# MAIN_TOP_P.net
KiCad netlist of a schematic drawn in EAGLE
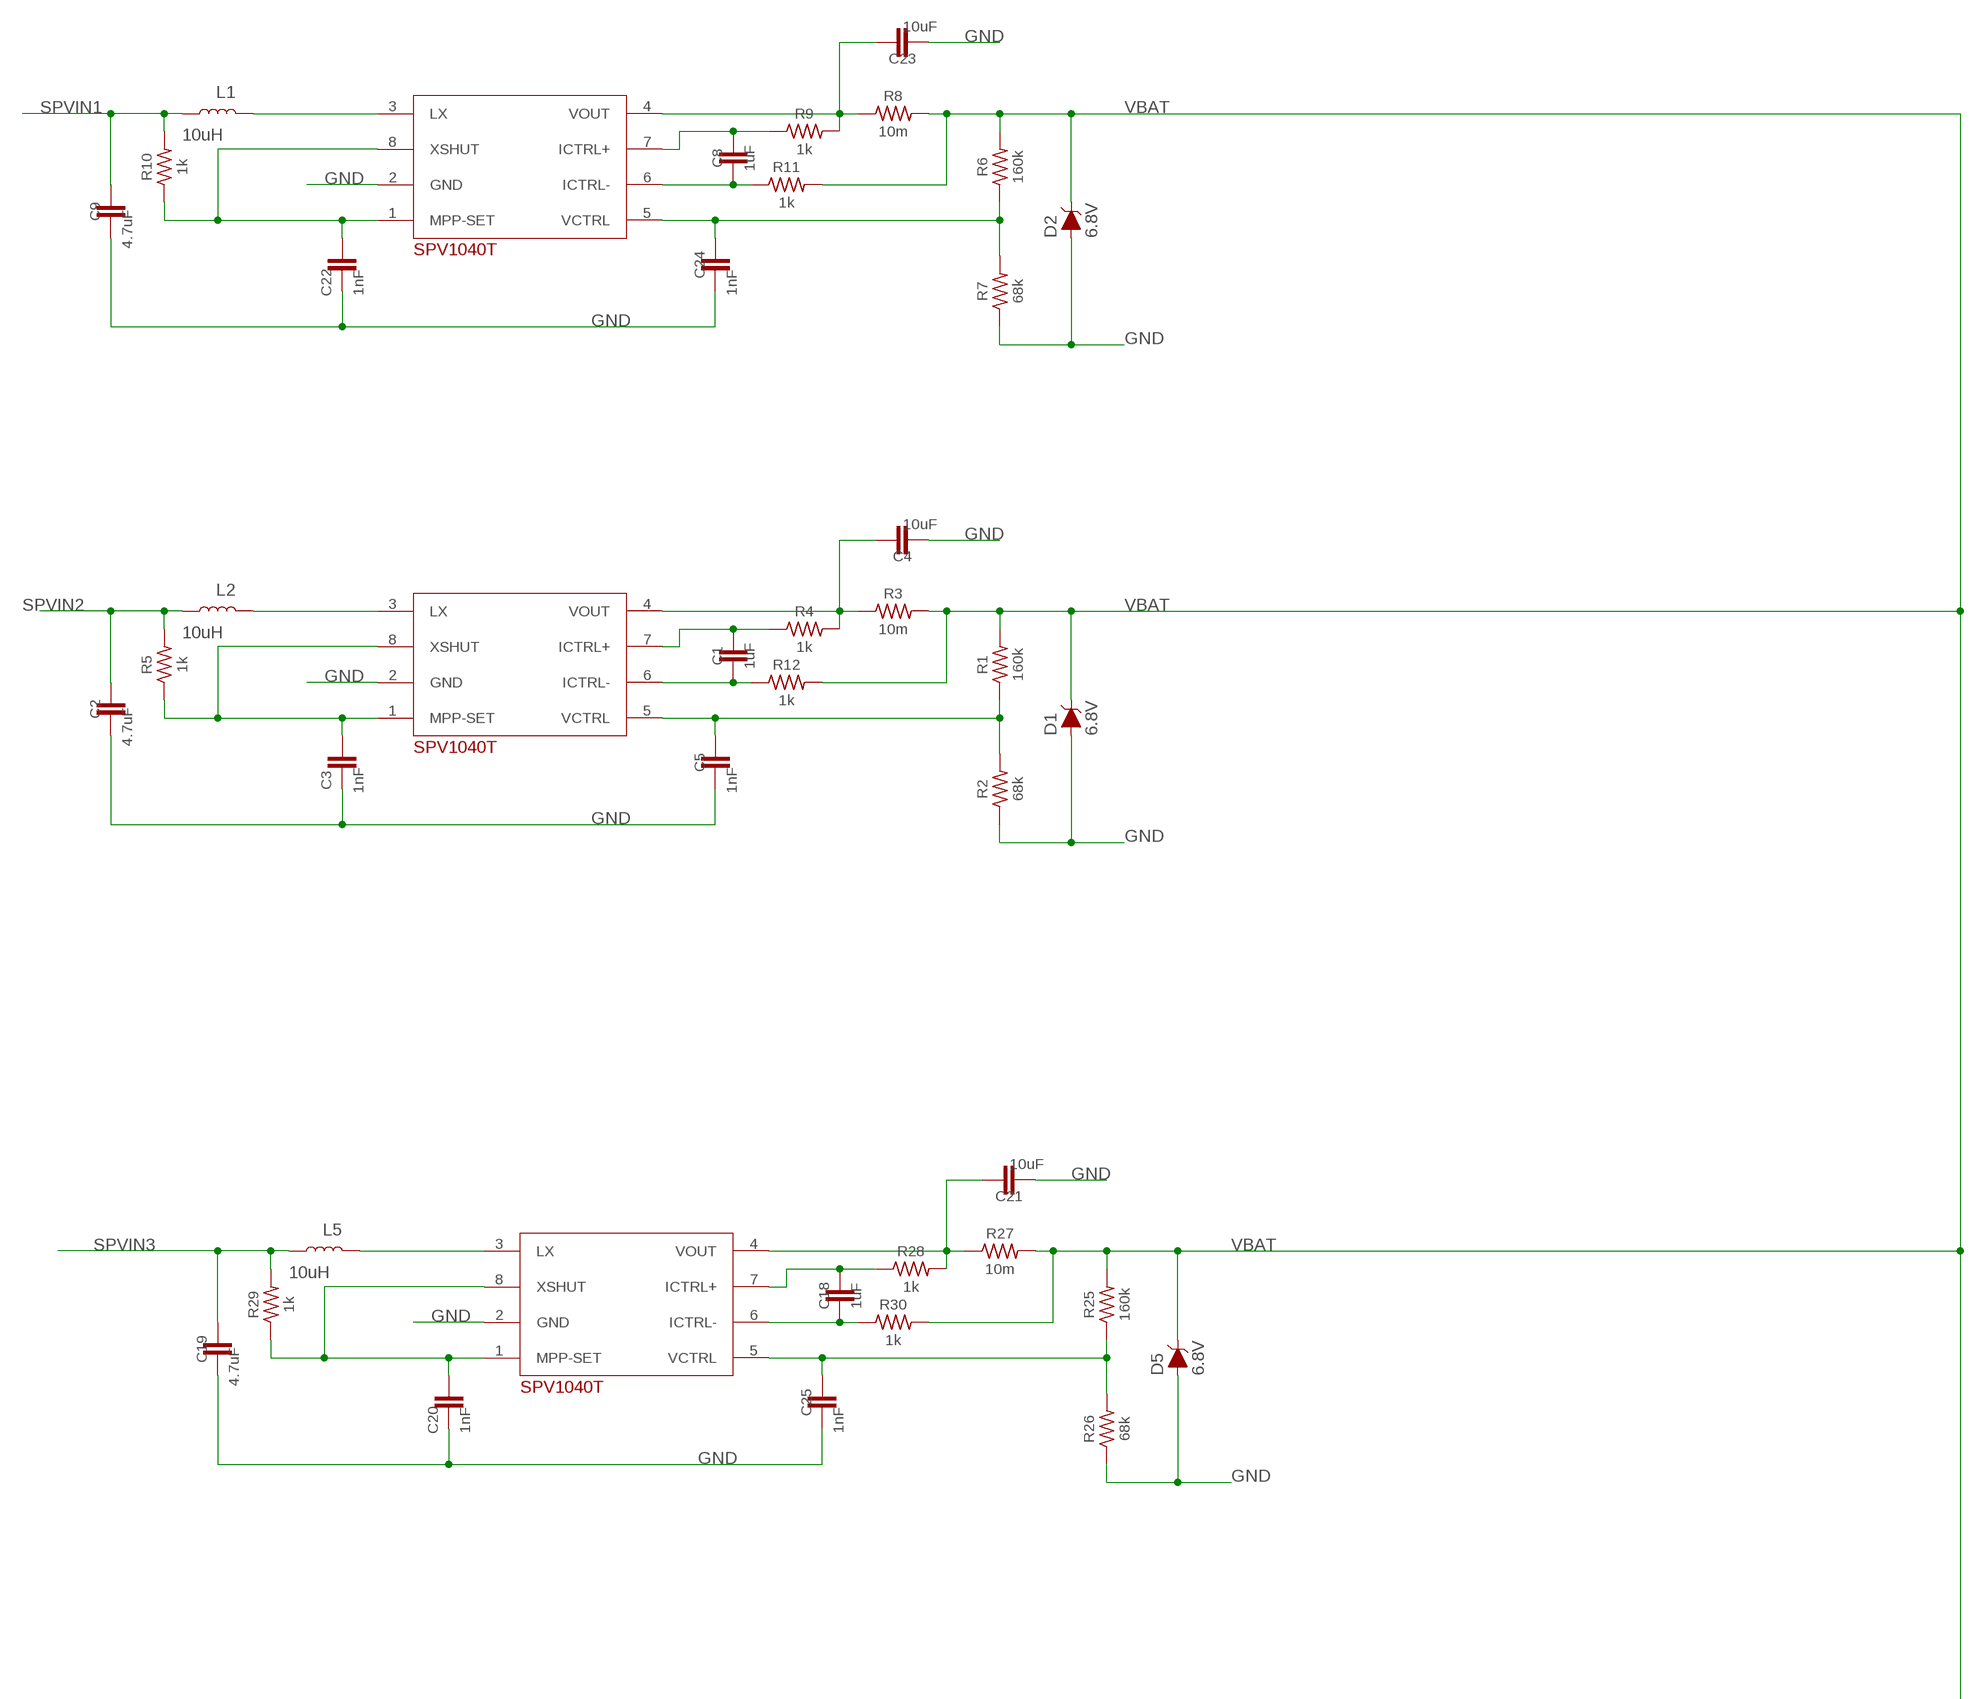
[diagram p0: schematic, sheet 1, part 1 of 3]
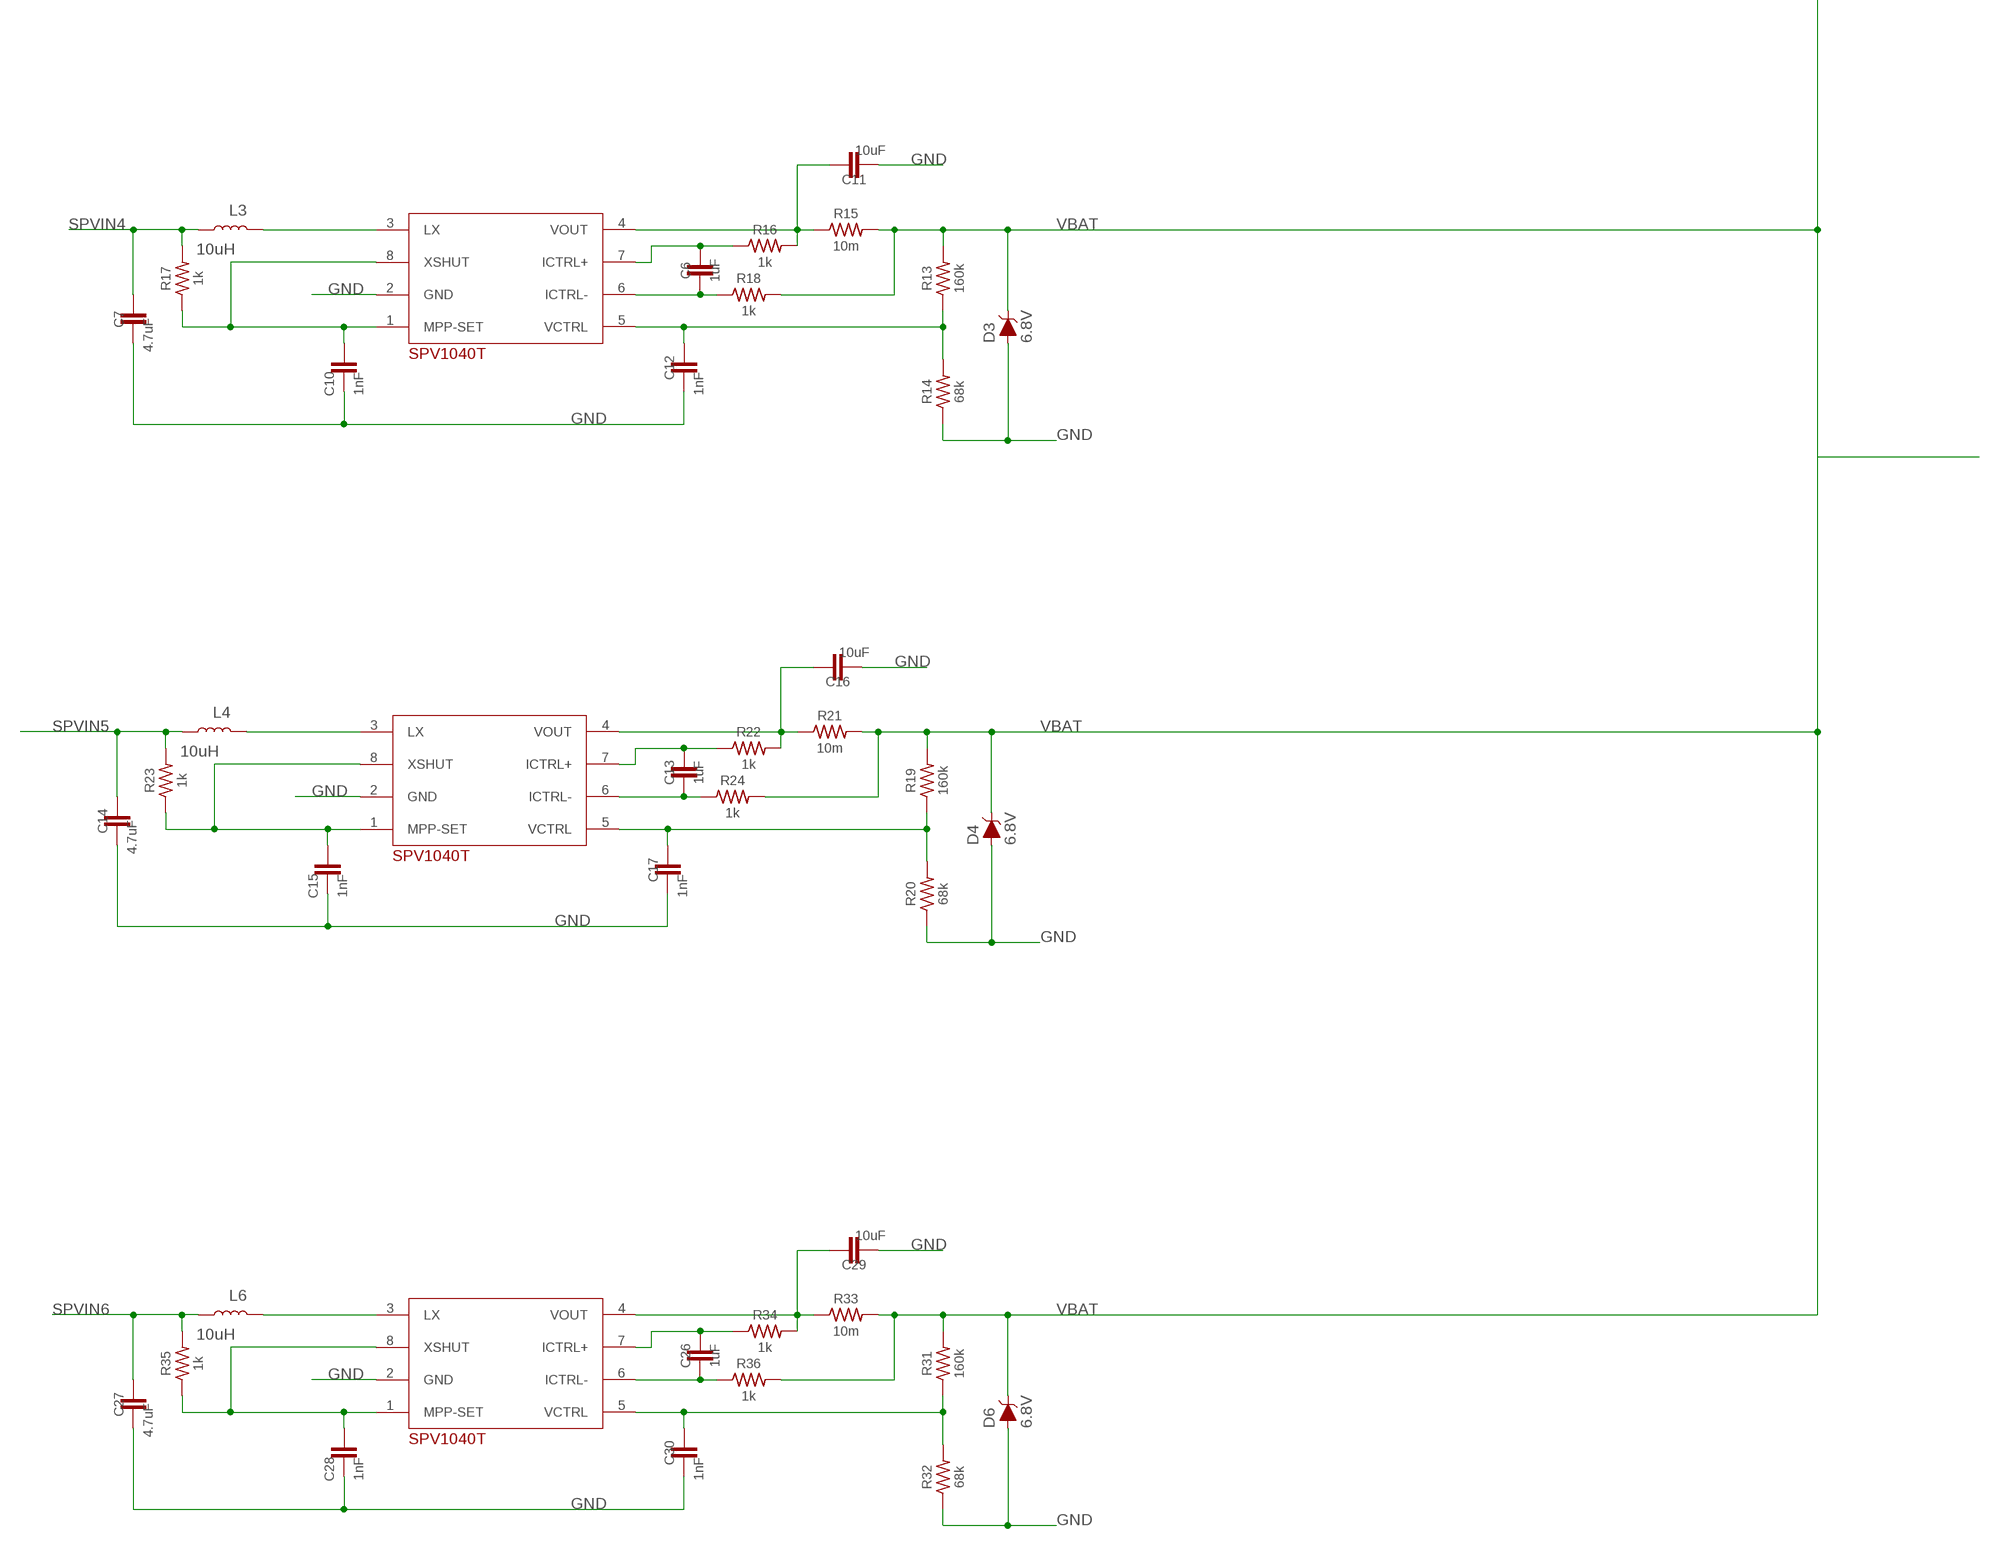
[diagram p1: schematic, sheet 1, part 2 of 3]
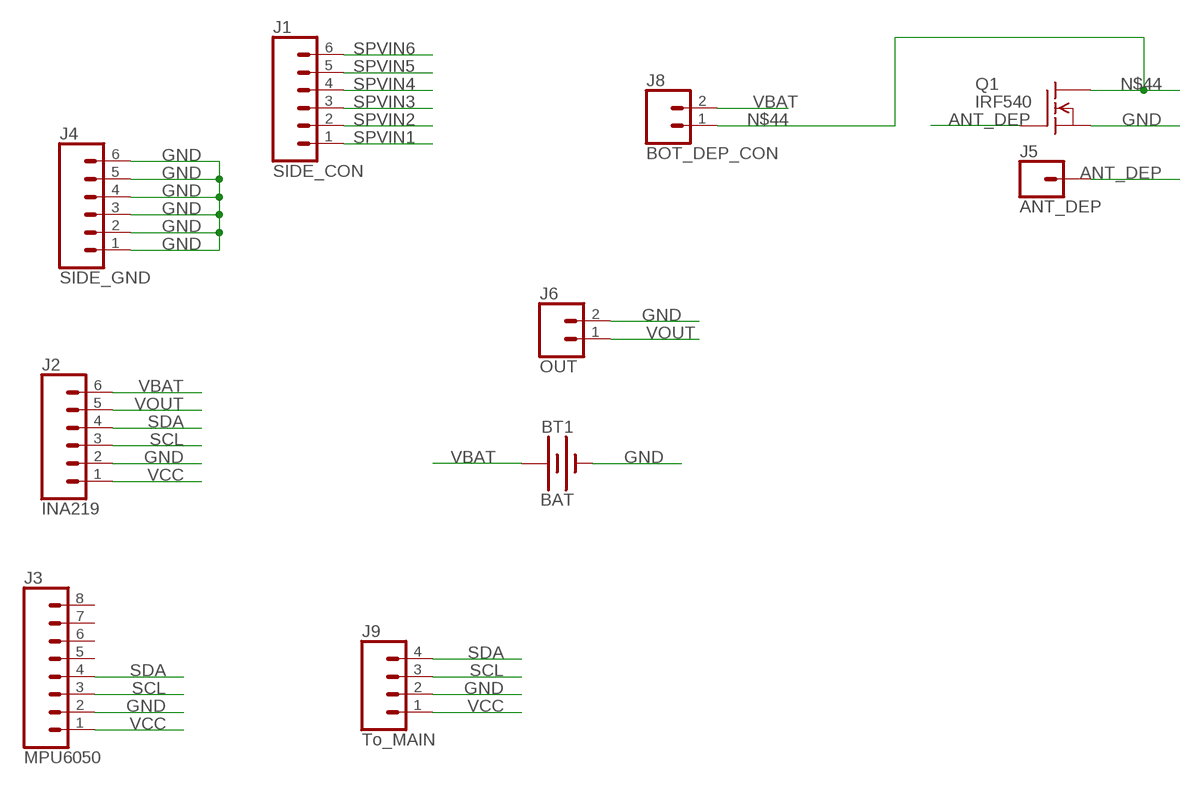
[diagram p2: schematic, sheet 1, part 3 of 3]

(export (version "E")
  (design (tool "Eeschema 10.0.6"))
  (components
    (comp (ref "BT1")
      (value "BAT")
      (footprint "eagle-import:BATTERY_18650-HOLDER")
      (libsource (lib "eagle-import") (part "BATTERY-18650"))
    )
    (comp (ref "C1")
      (value "1uF")
      (footprint "eagle-import:0603")
      (libsource (lib "eagle-import") (part "10UF-0603-6.3V-20%"))
    )
    (comp (ref "C2")
      (value "4.7uF")
      (footprint "eagle-import:0603")
      (libsource (lib "eagle-import") (part "10UF-0603-6.3V-20%"))
    )
    (comp (ref "C3")
      (value "1nF")
      (footprint "eagle-import:0603")
      (libsource (lib "eagle-import") (part "10UF-0603-6.3V-20%"))
    )
    (comp (ref "C4")
      (value "10uF")
      (footprint "eagle-import:0603")
      (libsource (lib "eagle-import") (part "10UF-0603-6.3V-20%"))
    )
    (comp (ref "C5")
      (value "1nF")
      (footprint "eagle-import:0603")
      (libsource (lib "eagle-import") (part "10UF-0603-6.3V-20%"))
    )
    (comp (ref "C6")
      (value "1uF")
      (footprint "eagle-import:0603")
      (libsource (lib "eagle-import") (part "10UF-0603-6.3V-20%"))
    )
    (comp (ref "C7")
      (value "4.7uF")
      (footprint "eagle-import:0603")
      (libsource (lib "eagle-import") (part "10UF-0603-6.3V-20%"))
    )
    (comp (ref "C8")
      (value "1uF")
      (footprint "eagle-import:0603")
      (libsource (lib "eagle-import") (part "10UF-0603-6.3V-20%"))
    )
    (comp (ref "C9")
      (value "4.7uF")
      (footprint "eagle-import:0603")
      (libsource (lib "eagle-import") (part "10UF-0603-6.3V-20%"))
    )
    (comp (ref "C10")
      (value "1nF")
      (footprint "eagle-import:0603")
      (libsource (lib "eagle-import") (part "10UF-0603-6.3V-20%"))
    )
    (comp (ref "C11")
      (value "10uF")
      (footprint "eagle-import:0603")
      (libsource (lib "eagle-import") (part "10UF-0603-6.3V-20%"))
    )
    (comp (ref "C12")
      (value "1nF")
      (footprint "eagle-import:0603")
      (libsource (lib "eagle-import") (part "10UF-0603-6.3V-20%"))
    )
    (comp (ref "C13")
      (value "1uF")
      (footprint "eagle-import:0603")
      (libsource (lib "eagle-import") (part "10UF-0603-6.3V-20%"))
    )
    (comp (ref "C14")
      (value "4.7uF")
      (footprint "eagle-import:0603")
      (libsource (lib "eagle-import") (part "10UF-0603-6.3V-20%"))
    )
    (comp (ref "C15")
      (value "1nF")
      (footprint "eagle-import:0603")
      (libsource (lib "eagle-import") (part "10UF-0603-6.3V-20%"))
    )
    (comp (ref "C16")
      (value "10uF")
      (footprint "eagle-import:0603")
      (libsource (lib "eagle-import") (part "10UF-0603-6.3V-20%"))
    )
    (comp (ref "C17")
      (value "1nF")
      (footprint "eagle-import:0603")
      (libsource (lib "eagle-import") (part "10UF-0603-6.3V-20%"))
    )
    (comp (ref "C18")
      (value "1uF")
      (footprint "eagle-import:0603")
      (libsource (lib "eagle-import") (part "10UF-0603-6.3V-20%"))
    )
    (comp (ref "C19")
      (value "4.7uF")
      (footprint "eagle-import:0603")
      (libsource (lib "eagle-import") (part "10UF-0603-6.3V-20%"))
    )
    (comp (ref "C20")
      (value "1nF")
      (footprint "eagle-import:0603")
      (libsource (lib "eagle-import") (part "10UF-0603-6.3V-20%"))
    )
    (comp (ref "C21")
      (value "10uF")
      (footprint "eagle-import:0603")
      (libsource (lib "eagle-import") (part "10UF-0603-6.3V-20%"))
    )
    (comp (ref "C22")
      (value "1nF")
      (footprint "eagle-import:0603")
      (libsource (lib "eagle-import") (part "10UF-0603-6.3V-20%"))
    )
    (comp (ref "C23")
      (value "10uF")
      (footprint "eagle-import:0603")
      (libsource (lib "eagle-import") (part "10UF-0603-6.3V-20%"))
    )
    (comp (ref "C24")
      (value "1nF")
      (footprint "eagle-import:0603")
      (libsource (lib "eagle-import") (part "10UF-0603-6.3V-20%"))
    )
    (comp (ref "C25")
      (value "1nF")
      (footprint "eagle-import:0603")
      (libsource (lib "eagle-import") (part "10UF-0603-6.3V-20%"))
    )
    (comp (ref "C26")
      (value "1uF")
      (footprint "eagle-import:0603")
      (libsource (lib "eagle-import") (part "10UF-0603-6.3V-20%"))
    )
    (comp (ref "C27")
      (value "4.7uF")
      (footprint "eagle-import:0603")
      (libsource (lib "eagle-import") (part "10UF-0603-6.3V-20%"))
    )
    (comp (ref "C28")
      (value "1nF")
      (footprint "eagle-import:0603")
      (libsource (lib "eagle-import") (part "10UF-0603-6.3V-20%"))
    )
    (comp (ref "C29")
      (value "10uF")
      (footprint "eagle-import:0603")
      (libsource (lib "eagle-import") (part "10UF-0603-6.3V-20%"))
    )
    (comp (ref "C30")
      (value "1nF")
      (footprint "eagle-import:0603")
      (libsource (lib "eagle-import") (part "10UF-0603-6.3V-20%"))
    )
    (comp (ref "D1")
      (value "6.8V")
      (footprint "eagle-import:SOD-323")
      (libsource (lib "eagle-import") (part "DIODE-ZENER-MMSZ5232BS"))
    )
    (comp (ref "D2")
      (value "6.8V")
      (footprint "eagle-import:SOD-323")
      (libsource (lib "eagle-import") (part "DIODE-ZENER-MMSZ5232BS"))
    )
    (comp (ref "D3")
      (value "6.8V")
      (footprint "eagle-import:SOD-323")
      (libsource (lib "eagle-import") (part "DIODE-ZENER-MMSZ5232BS"))
    )
    (comp (ref "D4")
      (value "6.8V")
      (footprint "eagle-import:SOD-323")
      (libsource (lib "eagle-import") (part "DIODE-ZENER-MMSZ5232BS"))
    )
    (comp (ref "D5")
      (value "6.8V")
      (footprint "eagle-import:SOD-323")
      (libsource (lib "eagle-import") (part "DIODE-ZENER-MMSZ5232BS"))
    )
    (comp (ref "D6")
      (value "6.8V")
      (footprint "eagle-import:SOD-323")
      (libsource (lib "eagle-import") (part "DIODE-ZENER-MMSZ5232BS"))
    )
    (comp (ref "J1")
      (value "SIDE_CON")
      (footprint "eagle-import:1X06")
      (libsource (lib "eagle-import") (part "CONN_06SILK_FEMALE_PTH"))
    )
    (comp (ref "J2")
      (value "INA219")
      (footprint "eagle-import:1X06")
      (libsource (lib "eagle-import") (part "CONN_06SILK_FEMALE_PTH"))
    )
    (comp (ref "J3")
      (value "MPU6050")
      (footprint "eagle-import:1X08")
      (libsource (lib "eagle-import") (part "CONN_08{dblquote}"))
    )
    (comp (ref "J4")
      (value "SIDE_GND")
      (footprint "eagle-import:1X06")
      (libsource (lib "eagle-import") (part "CONN_06SILK_FEMALE_PTH"))
    )
    (comp (ref "J5")
      (value "ANT_DEP")
      (footprint "eagle-import:1X01")
      (libsource (lib "eagle-import") (part "CONN_01"))
    )
    (comp (ref "J6")
      (value "OUT")
      (footprint "eagle-import:1X02")
      (libsource (lib "eagle-import") (part "CONN_02"))
    )
    (comp (ref "J8")
      (value "BOT_DEP_CON")
      (footprint "eagle-import:1X02")
      (libsource (lib "eagle-import") (part "CONN_02"))
    )
    (comp (ref "J9")
      (value "To_MAIN")
      (footprint "eagle-import:1X04")
      (libsource (lib "eagle-import") (part "CONN_04PTH"))
    )
    (comp (ref "L1")
      (value "10uH")
      (footprint "eagle-import:0603")
      (libsource (lib "eagle-import") (part "INDUCTOR-0603-33NH"))
    )
    (comp (ref "L2")
      (value "10uH")
      (footprint "eagle-import:0603")
      (libsource (lib "eagle-import") (part "INDUCTOR-0603-33NH"))
    )
    (comp (ref "L3")
      (value "10uH")
      (footprint "eagle-import:0603")
      (libsource (lib "eagle-import") (part "INDUCTOR-0603-33NH"))
    )
    (comp (ref "L4")
      (value "10uH")
      (footprint "eagle-import:0603")
      (libsource (lib "eagle-import") (part "INDUCTOR-0603-33NH"))
    )
    (comp (ref "L5")
      (value "10uH")
      (footprint "eagle-import:0603")
      (libsource (lib "eagle-import") (part "INDUCTOR-0603-33NH"))
    )
    (comp (ref "L6")
      (value "10uH")
      (footprint "eagle-import:0603")
      (libsource (lib "eagle-import") (part "INDUCTOR-0603-33NH"))
    )
    (comp (ref "Q1")
      (value "IRF540")
      (footprint "eagle-import:TO220")
      (libsource (lib "eagle-import") (part "IRF540"))
    )
    (comp (ref "R1")
      (value "160k")
      (footprint "eagle-import:RES_0603")
      (fields
        (field (name "DIGIKEY_PART_NUMBER") "311-0.0GRTR-ND")
        (field (name "MANUFACTURER") "Yageo")
        (field (name "MPN") "RC0603JR-070RL")
        (field (name "CREATED_BY") "PCBLayout.com")
      )
      (libsource (lib "eagle-import") (part "RC0603JR-070RL"))
    )
    (comp (ref "R2")
      (value "68k")
      (footprint "eagle-import:RES_0603")
      (fields
        (field (name "DIGIKEY_PART_NUMBER") "311-0.0GRTR-ND")
        (field (name "MANUFACTURER") "Yageo")
        (field (name "MPN") "RC0603JR-070RL")
        (field (name "CREATED_BY") "PCBLayout.com")
      )
      (libsource (lib "eagle-import") (part "RC0603JR-070RL"))
    )
    (comp (ref "R3")
      (value "10m")
      (footprint "eagle-import:RES_0603")
      (fields
        (field (name "DIGIKEY_PART_NUMBER") "311-0.0GRTR-ND")
        (field (name "MANUFACTURER") "Yageo")
        (field (name "MPN") "RC0603JR-070RL")
        (field (name "CREATED_BY") "PCBLayout.com")
      )
      (libsource (lib "eagle-import") (part "RC0603JR-070RL"))
    )
    (comp (ref "R4")
      (value "1k")
      (footprint "eagle-import:RES_0603")
      (fields
        (field (name "DIGIKEY_PART_NUMBER") "311-0.0GRTR-ND")
        (field (name "MANUFACTURER") "Yageo")
        (field (name "MPN") "RC0603JR-070RL")
        (field (name "CREATED_BY") "PCBLayout.com")
      )
      (libsource (lib "eagle-import") (part "RC0603JR-070RL"))
    )
    (comp (ref "R5")
      (value "1k")
      (footprint "eagle-import:RES_0603")
      (fields
        (field (name "DIGIKEY_PART_NUMBER") "311-0.0GRTR-ND")
        (field (name "MANUFACTURER") "Yageo")
        (field (name "MPN") "RC0603JR-070RL")
        (field (name "CREATED_BY") "PCBLayout.com")
      )
      (libsource (lib "eagle-import") (part "RC0603JR-070RL"))
    )
    (comp (ref "R6")
      (value "160k")
      (footprint "eagle-import:RES_0603")
      (fields
        (field (name "DIGIKEY_PART_NUMBER") "311-0.0GRTR-ND")
        (field (name "MANUFACTURER") "Yageo")
        (field (name "MPN") "RC0603JR-070RL")
        (field (name "CREATED_BY") "PCBLayout.com")
      )
      (libsource (lib "eagle-import") (part "RC0603JR-070RL"))
    )
    (comp (ref "R7")
      (value "68k")
      (footprint "eagle-import:RES_0603")
      (fields
        (field (name "DIGIKEY_PART_NUMBER") "311-0.0GRTR-ND")
        (field (name "MANUFACTURER") "Yageo")
        (field (name "MPN") "RC0603JR-070RL")
        (field (name "CREATED_BY") "PCBLayout.com")
      )
      (libsource (lib "eagle-import") (part "RC0603JR-070RL"))
    )
    (comp (ref "R8")
      (value "10m")
      (footprint "eagle-import:RES_0603")
      (fields
        (field (name "DIGIKEY_PART_NUMBER") "311-0.0GRTR-ND")
        (field (name "MANUFACTURER") "Yageo")
        (field (name "MPN") "RC0603JR-070RL")
        (field (name "CREATED_BY") "PCBLayout.com")
      )
      (libsource (lib "eagle-import") (part "RC0603JR-070RL"))
    )
    (comp (ref "R9")
      (value "1k")
      (footprint "eagle-import:RES_0603")
      (fields
        (field (name "DIGIKEY_PART_NUMBER") "311-0.0GRTR-ND")
        (field (name "MANUFACTURER") "Yageo")
        (field (name "MPN") "RC0603JR-070RL")
        (field (name "CREATED_BY") "PCBLayout.com")
      )
      (libsource (lib "eagle-import") (part "RC0603JR-070RL"))
    )
    (comp (ref "R10")
      (value "1k")
      (footprint "eagle-import:RES_0603")
      (fields
        (field (name "DIGIKEY_PART_NUMBER") "311-0.0GRTR-ND")
        (field (name "MANUFACTURER") "Yageo")
        (field (name "MPN") "RC0603JR-070RL")
        (field (name "CREATED_BY") "PCBLayout.com")
      )
      (libsource (lib "eagle-import") (part "RC0603JR-070RL"))
    )
    (comp (ref "R11")
      (value "1k")
      (footprint "eagle-import:RES_0603")
      (fields
        (field (name "DIGIKEY_PART_NUMBER") "311-0.0GRTR-ND")
        (field (name "MANUFACTURER") "Yageo")
        (field (name "MPN") "RC0603JR-070RL")
        (field (name "CREATED_BY") "PCBLayout.com")
      )
      (libsource (lib "eagle-import") (part "RC0603JR-070RL"))
    )
    (comp (ref "R12")
      (value "1k")
      (footprint "eagle-import:RES_0603")
      (fields
        (field (name "DIGIKEY_PART_NUMBER") "311-0.0GRTR-ND")
        (field (name "MANUFACTURER") "Yageo")
        (field (name "MPN") "RC0603JR-070RL")
        (field (name "CREATED_BY") "PCBLayout.com")
      )
      (libsource (lib "eagle-import") (part "RC0603JR-070RL"))
    )
    (comp (ref "R13")
      (value "160k")
      (footprint "eagle-import:RES_0603")
      (fields
        (field (name "DIGIKEY_PART_NUMBER") "311-0.0GRTR-ND")
        (field (name "MANUFACTURER") "Yageo")
        (field (name "MPN") "RC0603JR-070RL")
        (field (name "CREATED_BY") "PCBLayout.com")
      )
      (libsource (lib "eagle-import") (part "RC0603JR-070RL"))
    )
    (comp (ref "R14")
      (value "68k")
      (footprint "eagle-import:RES_0603")
      (fields
        (field (name "DIGIKEY_PART_NUMBER") "311-0.0GRTR-ND")
        (field (name "MANUFACTURER") "Yageo")
        (field (name "MPN") "RC0603JR-070RL")
        (field (name "CREATED_BY") "PCBLayout.com")
      )
      (libsource (lib "eagle-import") (part "RC0603JR-070RL"))
    )
    (comp (ref "R15")
      (value "10m")
      (footprint "eagle-import:RES_0603")
      (fields
        (field (name "DIGIKEY_PART_NUMBER") "311-0.0GRTR-ND")
        (field (name "MANUFACTURER") "Yageo")
        (field (name "MPN") "RC0603JR-070RL")
        (field (name "CREATED_BY") "PCBLayout.com")
      )
      (libsource (lib "eagle-import") (part "RC0603JR-070RL"))
    )
    (comp (ref "R16")
      (value "1k")
      (footprint "eagle-import:RES_0603")
      (fields
        (field (name "DIGIKEY_PART_NUMBER") "311-0.0GRTR-ND")
        (field (name "MANUFACTURER") "Yageo")
        (field (name "MPN") "RC0603JR-070RL")
        (field (name "CREATED_BY") "PCBLayout.com")
      )
      (libsource (lib "eagle-import") (part "RC0603JR-070RL"))
    )
    (comp (ref "R17")
      (value "1k")
      (footprint "eagle-import:RES_0603")
      (fields
        (field (name "DIGIKEY_PART_NUMBER") "311-0.0GRTR-ND")
        (field (name "MANUFACTURER") "Yageo")
        (field (name "MPN") "RC0603JR-070RL")
        (field (name "CREATED_BY") "PCBLayout.com")
      )
      (libsource (lib "eagle-import") (part "RC0603JR-070RL"))
    )
    (comp (ref "R18")
      (value "1k")
      (footprint "eagle-import:RES_0603")
      (fields
        (field (name "DIGIKEY_PART_NUMBER") "311-0.0GRTR-ND")
        (field (name "MANUFACTURER") "Yageo")
        (field (name "MPN") "RC0603JR-070RL")
        (field (name "CREATED_BY") "PCBLayout.com")
      )
      (libsource (lib "eagle-import") (part "RC0603JR-070RL"))
    )
    (comp (ref "R19")
      (value "160k")
      (footprint "eagle-import:RES_0603")
      (fields
        (field (name "DIGIKEY_PART_NUMBER") "311-0.0GRTR-ND")
        (field (name "MANUFACTURER") "Yageo")
        (field (name "MPN") "RC0603JR-070RL")
        (field (name "CREATED_BY") "PCBLayout.com")
      )
      (libsource (lib "eagle-import") (part "RC0603JR-070RL"))
    )
    (comp (ref "R20")
      (value "68k")
      (footprint "eagle-import:RES_0603")
      (fields
        (field (name "DIGIKEY_PART_NUMBER") "311-0.0GRTR-ND")
        (field (name "MANUFACTURER") "Yageo")
        (field (name "MPN") "RC0603JR-070RL")
        (field (name "CREATED_BY") "PCBLayout.com")
      )
      (libsource (lib "eagle-import") (part "RC0603JR-070RL"))
    )
    (comp (ref "R21")
      (value "10m")
      (footprint "eagle-import:RES_0603")
      (fields
        (field (name "DIGIKEY_PART_NUMBER") "311-0.0GRTR-ND")
        (field (name "MANUFACTURER") "Yageo")
        (field (name "MPN") "RC0603JR-070RL")
        (field (name "CREATED_BY") "PCBLayout.com")
      )
      (libsource (lib "eagle-import") (part "RC0603JR-070RL"))
    )
    (comp (ref "R22")
      (value "1k")
      (footprint "eagle-import:RES_0603")
      (fields
        (field (name "DIGIKEY_PART_NUMBER") "311-0.0GRTR-ND")
        (field (name "MANUFACTURER") "Yageo")
        (field (name "MPN") "RC0603JR-070RL")
        (field (name "CREATED_BY") "PCBLayout.com")
      )
      (libsource (lib "eagle-import") (part "RC0603JR-070RL"))
    )
    (comp (ref "R23")
      (value "1k")
      (footprint "eagle-import:RES_0603")
      (fields
        (field (name "DIGIKEY_PART_NUMBER") "311-0.0GRTR-ND")
        (field (name "MANUFACTURER") "Yageo")
        (field (name "MPN") "RC0603JR-070RL")
        (field (name "CREATED_BY") "PCBLayout.com")
      )
      (libsource (lib "eagle-import") (part "RC0603JR-070RL"))
    )
    (comp (ref "R24")
      (value "1k")
      (footprint "eagle-import:RES_0603")
      (fields
        (field (name "DIGIKEY_PART_NUMBER") "311-0.0GRTR-ND")
        (field (name "MANUFACTURER") "Yageo")
        (field (name "MPN") "RC0603JR-070RL")
        (field (name "CREATED_BY") "PCBLayout.com")
      )
      (libsource (lib "eagle-import") (part "RC0603JR-070RL"))
    )
    (comp (ref "R25")
      (value "160k")
      (footprint "eagle-import:RES_0603")
      (fields
        (field (name "DIGIKEY_PART_NUMBER") "311-0.0GRTR-ND")
        (field (name "MANUFACTURER") "Yageo")
        (field (name "MPN") "RC0603JR-070RL")
        (field (name "CREATED_BY") "PCBLayout.com")
      )
      (libsource (lib "eagle-import") (part "RC0603JR-070RL"))
    )
    (comp (ref "R26")
      (value "68k")
      (footprint "eagle-import:RES_0603")
      (fields
        (field (name "DIGIKEY_PART_NUMBER") "311-0.0GRTR-ND")
        (field (name "MANUFACTURER") "Yageo")
        (field (name "MPN") "RC0603JR-070RL")
        (field (name "CREATED_BY") "PCBLayout.com")
      )
      (libsource (lib "eagle-import") (part "RC0603JR-070RL"))
    )
    (comp (ref "R27")
      (value "10m")
      (footprint "eagle-import:RES_0603")
      (fields
        (field (name "DIGIKEY_PART_NUMBER") "311-0.0GRTR-ND")
        (field (name "MANUFACTURER") "Yageo")
        (field (name "MPN") "RC0603JR-070RL")
        (field (name "CREATED_BY") "PCBLayout.com")
      )
      (libsource (lib "eagle-import") (part "RC0603JR-070RL"))
    )
    (comp (ref "R28")
      (value "1k")
      (footprint "eagle-import:RES_0603")
      (fields
        (field (name "DIGIKEY_PART_NUMBER") "311-0.0GRTR-ND")
        (field (name "MANUFACTURER") "Yageo")
        (field (name "MPN") "RC0603JR-070RL")
        (field (name "CREATED_BY") "PCBLayout.com")
      )
      (libsource (lib "eagle-import") (part "RC0603JR-070RL"))
    )
    (comp (ref "R29")
      (value "1k")
      (footprint "eagle-import:RES_0603")
      (fields
        (field (name "DIGIKEY_PART_NUMBER") "311-0.0GRTR-ND")
        (field (name "MANUFACTURER") "Yageo")
        (field (name "MPN") "RC0603JR-070RL")
        (field (name "CREATED_BY") "PCBLayout.com")
      )
      (libsource (lib "eagle-import") (part "RC0603JR-070RL"))
    )
    (comp (ref "R30")
      (value "1k")
      (footprint "eagle-import:RES_0603")
      (fields
        (field (name "DIGIKEY_PART_NUMBER") "311-0.0GRTR-ND")
        (field (name "MANUFACTURER") "Yageo")
        (field (name "MPN") "RC0603JR-070RL")
        (field (name "CREATED_BY") "PCBLayout.com")
      )
      (libsource (lib "eagle-import") (part "RC0603JR-070RL"))
    )
    (comp (ref "R31")
      (value "160k")
      (footprint "eagle-import:RES_0603")
      (fields
        (field (name "DIGIKEY_PART_NUMBER") "311-0.0GRTR-ND")
        (field (name "MANUFACTURER") "Yageo")
        (field (name "MPN") "RC0603JR-070RL")
        (field (name "CREATED_BY") "PCBLayout.com")
      )
      (libsource (lib "eagle-import") (part "RC0603JR-070RL"))
    )
    (comp (ref "R32")
      (value "68k")
      (footprint "eagle-import:RES_0603")
      (fields
        (field (name "DIGIKEY_PART_NUMBER") "311-0.0GRTR-ND")
        (field (name "MANUFACTURER") "Yageo")
        (field (name "MPN") "RC0603JR-070RL")
        (field (name "CREATED_BY") "PCBLayout.com")
      )
      (libsource (lib "eagle-import") (part "RC0603JR-070RL"))
    )
    (comp (ref "R33")
      (value "10m")
      (footprint "eagle-import:RES_0603")
      (fields
        (field (name "DIGIKEY_PART_NUMBER") "311-0.0GRTR-ND")
        (field (name "MANUFACTURER") "Yageo")
        (field (name "MPN") "RC0603JR-070RL")
        (field (name "CREATED_BY") "PCBLayout.com")
      )
      (libsource (lib "eagle-import") (part "RC0603JR-070RL"))
    )
    (comp (ref "R34")
      (value "1k")
      (footprint "eagle-import:RES_0603")
      (fields
        (field (name "DIGIKEY_PART_NUMBER") "311-0.0GRTR-ND")
        (field (name "MANUFACTURER") "Yageo")
        (field (name "MPN") "RC0603JR-070RL")
        (field (name "CREATED_BY") "PCBLayout.com")
      )
      (libsource (lib "eagle-import") (part "RC0603JR-070RL"))
    )
    (comp (ref "R35")
      (value "1k")
      (footprint "eagle-import:RES_0603")
      (fields
        (field (name "DIGIKEY_PART_NUMBER") "311-0.0GRTR-ND")
        (field (name "MANUFACTURER") "Yageo")
        (field (name "MPN") "RC0603JR-070RL")
        (field (name "CREATED_BY") "PCBLayout.com")
      )
      (libsource (lib "eagle-import") (part "RC0603JR-070RL"))
    )
    (comp (ref "R36")
      (value "1k")
      (footprint "eagle-import:RES_0603")
      (fields
        (field (name "DIGIKEY_PART_NUMBER") "311-0.0GRTR-ND")
        (field (name "MANUFACTURER") "Yageo")
        (field (name "MPN") "RC0603JR-070RL")
        (field (name "CREATED_BY") "PCBLayout.com")
      )
      (libsource (lib "eagle-import") (part "RC0603JR-070RL"))
    )
    (comp (ref "SPV_1")
      (value "SPV1040T_")
      (footprint "eagle-import:SOP65P640X120-8N")
      (libsource (lib "eagle-import") (part "SPV1040T_"))
    )
    (comp (ref "SPV_2")
      (value "SPV1040T_")
      (footprint "eagle-import:SOP65P640X120-8N")
      (libsource (lib "eagle-import") (part "SPV1040T_"))
    )
    (comp (ref "SPV_3")
      (value "SPV1040T_")
      (footprint "eagle-import:SOP65P640X120-8N")
      (libsource (lib "eagle-import") (part "SPV1040T_"))
    )
    (comp (ref "SPV_4")
      (value "SPV1040T_")
      (footprint "eagle-import:SOP65P640X120-8N")
      (libsource (lib "eagle-import") (part "SPV1040T_"))
    )
    (comp (ref "SPV_5")
      (value "SPV1040T_")
      (footprint "eagle-import:SOP65P640X120-8N")
      (libsource (lib "eagle-import") (part "SPV1040T_"))
    )
    (comp (ref "SPV_6")
      (value "SPV1040T_")
      (footprint "eagle-import:SOP65P640X120-8N")
      (libsource (lib "eagle-import") (part "SPV1040T_"))
    )
  )
  (nets
    (net (code "1") (name "/ANT_DEP") (class "Default")
      (node (ref "J5") (pin "1") (pinfunction "1_1") (pintype "passive"))
      (node (ref "Q1") (pin "1") (pinfunction "G_1") (pintype "passive"))
    )
    (net (code "2") (name "/GND") (class "Default")
      (node (ref "BT1") (pin "GND@1") (pinfunction "-_GND@1") (pintype "power_in"))
      (node (ref "C10") (pin "2") (pinfunction "2_2") (pintype "passive"))
      (node (ref "C11") (pin "2") (pinfunction "2_2") (pintype "passive"))
      (node (ref "C12") (pin "2") (pinfunction "2_2") (pintype "passive"))
      (node (ref "C14") (pin "2") (pinfunction "2_2") (pintype "passive"))
      (node (ref "C15") (pin "2") (pinfunction "2_2") (pintype "passive"))
      (node (ref "C16") (pin "2") (pinfunction "2_2") (pintype "passive"))
      (node (ref "C17") (pin "2") (pinfunction "2_2") (pintype "passive"))
      (node (ref "C19") (pin "2") (pinfunction "2_2") (pintype "passive"))
      (node (ref "C2") (pin "2") (pinfunction "2_2") (pintype "passive"))
      (node (ref "C20") (pin "2") (pinfunction "2_2") (pintype "passive"))
      (node (ref "C21") (pin "2") (pinfunction "2_2") (pintype "passive"))
      (node (ref "C22") (pin "2") (pinfunction "2_2") (pintype "passive"))
      (node (ref "C23") (pin "2") (pinfunction "2_2") (pintype "passive"))
      (node (ref "C24") (pin "2") (pinfunction "2_2") (pintype "passive"))
      (node (ref "C25") (pin "2") (pinfunction "2_2") (pintype "passive"))
      (node (ref "C27") (pin "2") (pinfunction "2_2") (pintype "passive"))
      (node (ref "C28") (pin "2") (pinfunction "2_2") (pintype "passive"))
      (node (ref "C29") (pin "2") (pinfunction "2_2") (pintype "passive"))
      (node (ref "C3") (pin "2") (pinfunction "2_2") (pintype "passive"))
      (node (ref "C30") (pin "2") (pinfunction "2_2") (pintype "passive"))
      (node (ref "C4") (pin "2") (pinfunction "2_2") (pintype "passive"))
      (node (ref "C5") (pin "2") (pinfunction "2_2") (pintype "passive"))
      (node (ref "C7") (pin "2") (pinfunction "2_2") (pintype "passive"))
      (node (ref "C9") (pin "2") (pinfunction "2_2") (pintype "passive"))
      (node (ref "D1") (pin "A") (pinfunction "A_A") (pintype "passive"))
      (node (ref "D2") (pin "A") (pinfunction "A_A") (pintype "passive"))
      (node (ref "D3") (pin "A") (pinfunction "A_A") (pintype "passive"))
      (node (ref "D4") (pin "A") (pinfunction "A_A") (pintype "passive"))
      (node (ref "D5") (pin "A") (pinfunction "A_A") (pintype "passive"))
      (node (ref "D6") (pin "A") (pinfunction "A_A") (pintype "passive"))
      (node (ref "J2") (pin "2") (pinfunction "2_2") (pintype "passive"))
      (node (ref "J3") (pin "2") (pinfunction "2_2") (pintype "passive"))
      (node (ref "J4") (pin "1") (pinfunction "1_1") (pintype "passive"))
      (node (ref "J4") (pin "2") (pinfunction "2_2") (pintype "passive"))
      (node (ref "J4") (pin "3") (pinfunction "3_3") (pintype "passive"))
      (node (ref "J4") (pin "4") (pinfunction "4_4") (pintype "passive"))
      (node (ref "J4") (pin "5") (pinfunction "5_5") (pintype "passive"))
      (node (ref "J4") (pin "6") (pinfunction "6_6") (pintype "passive"))
      (node (ref "J6") (pin "2") (pinfunction "2_2") (pintype "passive"))
      (node (ref "J9") (pin "2") (pinfunction "2_2") (pintype "passive"))
      (node (ref "Q1") (pin "3") (pinfunction "S_3") (pintype "passive"))
      (node (ref "R14") (pin "1") (pinfunction "1_1") (pintype "passive"))
      (node (ref "R2") (pin "1") (pinfunction "1_1") (pintype "passive"))
      (node (ref "R20") (pin "1") (pinfunction "1_1") (pintype "passive"))
      (node (ref "R26") (pin "1") (pinfunction "1_1") (pintype "passive"))
      (node (ref "R32") (pin "1") (pinfunction "1_1") (pintype "passive"))
      (node (ref "R7") (pin "1") (pinfunction "1_1") (pintype "passive"))
      (node (ref "SPV_1") (pin "2") (pinfunction "GND_2") (pintype "bidirectional"))
      (node (ref "SPV_2") (pin "2") (pinfunction "GND_2") (pintype "bidirectional"))
      (node (ref "SPV_3") (pin "2") (pinfunction "GND_2") (pintype "bidirectional"))
      (node (ref "SPV_4") (pin "2") (pinfunction "GND_2") (pintype "bidirectional"))
      (node (ref "SPV_5") (pin "2") (pinfunction "GND_2") (pintype "bidirectional"))
      (node (ref "SPV_6") (pin "2") (pinfunction "GND_2") (pintype "bidirectional"))
    )
    (net (code "3") (name "/N$44") (class "Default")
      (node (ref "J8") (pin "1") (pinfunction "1_1") (pintype "passive"))
      (node (ref "Q1") (pin "2") (pinfunction "D_2") (pintype "passive"))
    )
    (net (code "4") (name "/SCL") (class "Default")
      (node (ref "J2") (pin "3") (pinfunction "3_3") (pintype "passive"))
      (node (ref "J3") (pin "3") (pinfunction "3_3") (pintype "passive"))
      (node (ref "J9") (pin "3") (pinfunction "3_3") (pintype "passive"))
    )
    (net (code "5") (name "/SDA") (class "Default")
      (node (ref "J2") (pin "4") (pinfunction "4_4") (pintype "passive"))
      (node (ref "J3") (pin "4") (pinfunction "4_4") (pintype "passive"))
      (node (ref "J9") (pin "4") (pinfunction "4_4") (pintype "passive"))
    )
    (net (code "6") (name "/SPVIN1") (class "Default")
      (node (ref "C9") (pin "1") (pinfunction "1_1") (pintype "passive"))
      (node (ref "J1") (pin "1") (pinfunction "1_1") (pintype "passive"))
      (node (ref "L1") (pin "1") (pinfunction "1_1") (pintype "passive"))
      (node (ref "R10") (pin "2") (pinfunction "2_2") (pintype "passive"))
    )
    (net (code "7") (name "/SPVIN2") (class "Default")
      (node (ref "C2") (pin "1") (pinfunction "1_1") (pintype "passive"))
      (node (ref "J1") (pin "2") (pinfunction "2_2") (pintype "passive"))
      (node (ref "L2") (pin "1") (pinfunction "1_1") (pintype "passive"))
      (node (ref "R5") (pin "2") (pinfunction "2_2") (pintype "passive"))
    )
    (net (code "8") (name "/SPVIN3") (class "Default")
      (node (ref "C19") (pin "1") (pinfunction "1_1") (pintype "passive"))
      (node (ref "J1") (pin "3") (pinfunction "3_3") (pintype "passive"))
      (node (ref "L5") (pin "1") (pinfunction "1_1") (pintype "passive"))
      (node (ref "R29") (pin "2") (pinfunction "2_2") (pintype "passive"))
    )
    (net (code "9") (name "/SPVIN4") (class "Default")
      (node (ref "C7") (pin "1") (pinfunction "1_1") (pintype "passive"))
      (node (ref "J1") (pin "4") (pinfunction "4_4") (pintype "passive"))
      (node (ref "L3") (pin "1") (pinfunction "1_1") (pintype "passive"))
      (node (ref "R17") (pin "2") (pinfunction "2_2") (pintype "passive"))
    )
    (net (code "10") (name "/SPVIN5") (class "Default")
      (node (ref "C14") (pin "1") (pinfunction "1_1") (pintype "passive"))
      (node (ref "J1") (pin "5") (pinfunction "5_5") (pintype "passive"))
      (node (ref "L4") (pin "1") (pinfunction "1_1") (pintype "passive"))
      (node (ref "R23") (pin "2") (pinfunction "2_2") (pintype "passive"))
    )
    (net (code "11") (name "/SPVIN6") (class "Default")
      (node (ref "C27") (pin "1") (pinfunction "1_1") (pintype "passive"))
      (node (ref "J1") (pin "6") (pinfunction "6_6") (pintype "passive"))
      (node (ref "L6") (pin "1") (pinfunction "1_1") (pintype "passive"))
      (node (ref "R35") (pin "2") (pinfunction "2_2") (pintype "passive"))
    )
    (net (code "12") (name "/VBAT") (class "Default")
      (node (ref "BT1") (pin "PWR@1") (pinfunction "+_PWR@1") (pintype "power_in"))
      (node (ref "D1") (pin "C") (pinfunction "C_C") (pintype "passive"))
      (node (ref "D2") (pin "C") (pinfunction "C_C") (pintype "passive"))
      (node (ref "D3") (pin "C") (pinfunction "C_C") (pintype "passive"))
      (node (ref "D4") (pin "C") (pinfunction "C_C") (pintype "passive"))
      (node (ref "D5") (pin "C") (pinfunction "C_C") (pintype "passive"))
      (node (ref "D6") (pin "C") (pinfunction "C_C") (pintype "passive"))
      (node (ref "J2") (pin "6") (pinfunction "6_6") (pintype "passive"))
      (node (ref "J8") (pin "2") (pinfunction "2_2") (pintype "passive"))
      (node (ref "R1") (pin "2") (pinfunction "2_2") (pintype "passive"))
      (node (ref "R11") (pin "2") (pinfunction "2_2") (pintype "passive"))
      (node (ref "R12") (pin "2") (pinfunction "2_2") (pintype "passive"))
      (node (ref "R13") (pin "2") (pinfunction "2_2") (pintype "passive"))
      (node (ref "R15") (pin "2") (pinfunction "2_2") (pintype "passive"))
      (node (ref "R18") (pin "2") (pinfunction "2_2") (pintype "passive"))
      (node (ref "R19") (pin "2") (pinfunction "2_2") (pintype "passive"))
      (node (ref "R21") (pin "2") (pinfunction "2_2") (pintype "passive"))
      (node (ref "R24") (pin "2") (pinfunction "2_2") (pintype "passive"))
      (node (ref "R25") (pin "2") (pinfunction "2_2") (pintype "passive"))
      (node (ref "R27") (pin "2") (pinfunction "2_2") (pintype "passive"))
      (node (ref "R3") (pin "2") (pinfunction "2_2") (pintype "passive"))
      (node (ref "R30") (pin "2") (pinfunction "2_2") (pintype "passive"))
      (node (ref "R31") (pin "2") (pinfunction "2_2") (pintype "passive"))
      (node (ref "R33") (pin "2") (pinfunction "2_2") (pintype "passive"))
      (node (ref "R36") (pin "2") (pinfunction "2_2") (pintype "passive"))
      (node (ref "R6") (pin "2") (pinfunction "2_2") (pintype "passive"))
      (node (ref "R8") (pin "2") (pinfunction "2_2") (pintype "passive"))
    )
    (net (code "13") (name "/VCC") (class "Default")
      (node (ref "J2") (pin "1") (pinfunction "1_1") (pintype "passive"))
      (node (ref "J3") (pin "1") (pinfunction "1_1") (pintype "passive"))
      (node (ref "J9") (pin "1") (pinfunction "1_1") (pintype "passive"))
    )
    (net (code "14") (name "/VOUT") (class "Default")
      (node (ref "J2") (pin "5") (pinfunction "5_5") (pintype "passive"))
      (node (ref "J6") (pin "1") (pinfunction "1_1") (pintype "passive"))
    )
    (net (code "15") (name "Net-(SPV_1-ICTRL+)") (class "Default")
      (node (ref "C8") (pin "1") (pinfunction "1_1") (pintype "passive"))
      (node (ref "R9") (pin "1") (pinfunction "1_1") (pintype "passive"))
      (node (ref "SPV_1") (pin "7") (pinfunction "ICTRL+_7") (pintype "bidirectional"))
    )
    (net (code "16") (name "Net-(SPV_1-ICTRL-)") (class "Default")
      (node (ref "C8") (pin "2") (pinfunction "2_2") (pintype "passive"))
      (node (ref "R11") (pin "1") (pinfunction "1_1") (pintype "passive"))
      (node (ref "SPV_1") (pin "6") (pinfunction "ICTRL-_6") (pintype "bidirectional"))
    )
    (net (code "17") (name "Net-(SPV_1-LX)") (class "Default")
      (node (ref "L1") (pin "2") (pinfunction "2_2") (pintype "passive"))
      (node (ref "SPV_1") (pin "3") (pinfunction "LX_3") (pintype "bidirectional"))
    )
    (net (code "18") (name "Net-(SPV_1-MPP-SET)") (class "Default")
      (node (ref "C22") (pin "1") (pinfunction "1_1") (pintype "passive"))
      (node (ref "R10") (pin "1") (pinfunction "1_1") (pintype "passive"))
      (node (ref "SPV_1") (pin "1") (pinfunction "MPP-SET_1") (pintype "bidirectional"))
      (node (ref "SPV_1") (pin "8") (pinfunction "XSHUT_8") (pintype "bidirectional"))
    )
    (net (code "19") (name "Net-(SPV_1-VCTRL)") (class "Default")
      (node (ref "C24") (pin "1") (pinfunction "1_1") (pintype "passive"))
      (node (ref "R6") (pin "1") (pinfunction "1_1") (pintype "passive"))
      (node (ref "R7") (pin "2") (pinfunction "2_2") (pintype "passive"))
      (node (ref "SPV_1") (pin "5") (pinfunction "VCTRL_5") (pintype "bidirectional"))
    )
    (net (code "20") (name "Net-(SPV_1-VOUT)") (class "Default")
      (node (ref "C23") (pin "1") (pinfunction "1_1") (pintype "passive"))
      (node (ref "R8") (pin "1") (pinfunction "1_1") (pintype "passive"))
      (node (ref "R9") (pin "2") (pinfunction "2_2") (pintype "passive"))
      (node (ref "SPV_1") (pin "4") (pinfunction "VOUT_4") (pintype "bidirectional"))
    )
    (net (code "21") (name "Net-(SPV_2-ICTRL+)") (class "Default")
      (node (ref "C1") (pin "1") (pinfunction "1_1") (pintype "passive"))
      (node (ref "R4") (pin "1") (pinfunction "1_1") (pintype "passive"))
      (node (ref "SPV_2") (pin "7") (pinfunction "ICTRL+_7") (pintype "bidirectional"))
    )
    (net (code "22") (name "Net-(SPV_2-ICTRL-)") (class "Default")
      (node (ref "C1") (pin "2") (pinfunction "2_2") (pintype "passive"))
      (node (ref "R12") (pin "1") (pinfunction "1_1") (pintype "passive"))
      (node (ref "SPV_2") (pin "6") (pinfunction "ICTRL-_6") (pintype "bidirectional"))
    )
    (net (code "23") (name "Net-(SPV_2-LX)") (class "Default")
      (node (ref "L2") (pin "2") (pinfunction "2_2") (pintype "passive"))
      (node (ref "SPV_2") (pin "3") (pinfunction "LX_3") (pintype "bidirectional"))
    )
    (net (code "24") (name "Net-(SPV_2-MPP-SET)") (class "Default")
      (node (ref "C3") (pin "1") (pinfunction "1_1") (pintype "passive"))
      (node (ref "R5") (pin "1") (pinfunction "1_1") (pintype "passive"))
      (node (ref "SPV_2") (pin "1") (pinfunction "MPP-SET_1") (pintype "bidirectional"))
      (node (ref "SPV_2") (pin "8") (pinfunction "XSHUT_8") (pintype "bidirectional"))
    )
    (net (code "25") (name "Net-(SPV_2-VCTRL)") (class "Default")
      (node (ref "C5") (pin "1") (pinfunction "1_1") (pintype "passive"))
      (node (ref "R1") (pin "1") (pinfunction "1_1") (pintype "passive"))
      (node (ref "R2") (pin "2") (pinfunction "2_2") (pintype "passive"))
      (node (ref "SPV_2") (pin "5") (pinfunction "VCTRL_5") (pintype "bidirectional"))
    )
    (net (code "26") (name "Net-(SPV_2-VOUT)") (class "Default")
      (node (ref "C4") (pin "1") (pinfunction "1_1") (pintype "passive"))
      (node (ref "R3") (pin "1") (pinfunction "1_1") (pintype "passive"))
      (node (ref "R4") (pin "2") (pinfunction "2_2") (pintype "passive"))
      (node (ref "SPV_2") (pin "4") (pinfunction "VOUT_4") (pintype "bidirectional"))
    )
    (net (code "27") (name "Net-(SPV_3-ICTRL+)") (class "Default")
      (node (ref "C18") (pin "1") (pinfunction "1_1") (pintype "passive"))
      (node (ref "R28") (pin "1") (pinfunction "1_1") (pintype "passive"))
      (node (ref "SPV_3") (pin "7") (pinfunction "ICTRL+_7") (pintype "bidirectional"))
    )
    (net (code "28") (name "Net-(SPV_3-ICTRL-)") (class "Default")
      (node (ref "C18") (pin "2") (pinfunction "2_2") (pintype "passive"))
      (node (ref "R30") (pin "1") (pinfunction "1_1") (pintype "passive"))
      (node (ref "SPV_3") (pin "6") (pinfunction "ICTRL-_6") (pintype "bidirectional"))
    )
    (net (code "29") (name "Net-(SPV_3-LX)") (class "Default")
      (node (ref "L5") (pin "2") (pinfunction "2_2") (pintype "passive"))
      (node (ref "SPV_3") (pin "3") (pinfunction "LX_3") (pintype "bidirectional"))
    )
    (net (code "30") (name "Net-(SPV_3-MPP-SET)") (class "Default")
      (node (ref "C20") (pin "1") (pinfunction "1_1") (pintype "passive"))
      (node (ref "R29") (pin "1") (pinfunction "1_1") (pintype "passive"))
      (node (ref "SPV_3") (pin "1") (pinfunction "MPP-SET_1") (pintype "bidirectional"))
      (node (ref "SPV_3") (pin "8") (pinfunction "XSHUT_8") (pintype "bidirectional"))
    )
    (net (code "31") (name "Net-(SPV_3-VCTRL)") (class "Default")
      (node (ref "C25") (pin "1") (pinfunction "1_1") (pintype "passive"))
      (node (ref "R25") (pin "1") (pinfunction "1_1") (pintype "passive"))
      (node (ref "R26") (pin "2") (pinfunction "2_2") (pintype "passive"))
      (node (ref "SPV_3") (pin "5") (pinfunction "VCTRL_5") (pintype "bidirectional"))
    )
    (net (code "32") (name "Net-(SPV_3-VOUT)") (class "Default")
      (node (ref "C21") (pin "1") (pinfunction "1_1") (pintype "passive"))
      (node (ref "R27") (pin "1") (pinfunction "1_1") (pintype "passive"))
      (node (ref "R28") (pin "2") (pinfunction "2_2") (pintype "passive"))
      (node (ref "SPV_3") (pin "4") (pinfunction "VOUT_4") (pintype "bidirectional"))
    )
    (net (code "33") (name "Net-(SPV_4-ICTRL+)") (class "Default")
      (node (ref "C6") (pin "1") (pinfunction "1_1") (pintype "passive"))
      (node (ref "R16") (pin "1") (pinfunction "1_1") (pintype "passive"))
      (node (ref "SPV_4") (pin "7") (pinfunction "ICTRL+_7") (pintype "bidirectional"))
    )
    (net (code "34") (name "Net-(SPV_4-ICTRL-)") (class "Default")
      (node (ref "C6") (pin "2") (pinfunction "2_2") (pintype "passive"))
      (node (ref "R18") (pin "1") (pinfunction "1_1") (pintype "passive"))
      (node (ref "SPV_4") (pin "6") (pinfunction "ICTRL-_6") (pintype "bidirectional"))
    )
    (net (code "35") (name "Net-(SPV_4-LX)") (class "Default")
      (node (ref "L3") (pin "2") (pinfunction "2_2") (pintype "passive"))
      (node (ref "SPV_4") (pin "3") (pinfunction "LX_3") (pintype "bidirectional"))
    )
    (net (code "36") (name "Net-(SPV_4-MPP-SET)") (class "Default")
      (node (ref "C10") (pin "1") (pinfunction "1_1") (pintype "passive"))
      (node (ref "R17") (pin "1") (pinfunction "1_1") (pintype "passive"))
      (node (ref "SPV_4") (pin "1") (pinfunction "MPP-SET_1") (pintype "bidirectional"))
      (node (ref "SPV_4") (pin "8") (pinfunction "XSHUT_8") (pintype "bidirectional"))
    )
    (net (code "37") (name "Net-(SPV_4-VCTRL)") (class "Default")
      (node (ref "C12") (pin "1") (pinfunction "1_1") (pintype "passive"))
      (node (ref "R13") (pin "1") (pinfunction "1_1") (pintype "passive"))
      (node (ref "R14") (pin "2") (pinfunction "2_2") (pintype "passive"))
      (node (ref "SPV_4") (pin "5") (pinfunction "VCTRL_5") (pintype "bidirectional"))
    )
    (net (code "38") (name "Net-(SPV_4-VOUT)") (class "Default")
      (node (ref "C11") (pin "1") (pinfunction "1_1") (pintype "passive"))
      (node (ref "R15") (pin "1") (pinfunction "1_1") (pintype "passive"))
      (node (ref "R16") (pin "2") (pinfunction "2_2") (pintype "passive"))
      (node (ref "SPV_4") (pin "4") (pinfunction "VOUT_4") (pintype "bidirectional"))
    )
    (net (code "39") (name "Net-(SPV_5-ICTRL+)") (class "Default")
      (node (ref "C13") (pin "1") (pinfunction "1_1") (pintype "passive"))
      (node (ref "R22") (pin "1") (pinfunction "1_1") (pintype "passive"))
      (node (ref "SPV_5") (pin "7") (pinfunction "ICTRL+_7") (pintype "bidirectional"))
    )
    (net (code "40") (name "Net-(SPV_5-ICTRL-)") (class "Default")
      (node (ref "C13") (pin "2") (pinfunction "2_2") (pintype "passive"))
      (node (ref "R24") (pin "1") (pinfunction "1_1") (pintype "passive"))
      (node (ref "SPV_5") (pin "6") (pinfunction "ICTRL-_6") (pintype "bidirectional"))
    )
    (net (code "41") (name "Net-(SPV_5-LX)") (class "Default")
      (node (ref "L4") (pin "2") (pinfunction "2_2") (pintype "passive"))
      (node (ref "SPV_5") (pin "3") (pinfunction "LX_3") (pintype "bidirectional"))
    )
    (net (code "42") (name "Net-(SPV_5-MPP-SET)") (class "Default")
      (node (ref "C15") (pin "1") (pinfunction "1_1") (pintype "passive"))
      (node (ref "R23") (pin "1") (pinfunction "1_1") (pintype "passive"))
      (node (ref "SPV_5") (pin "1") (pinfunction "MPP-SET_1") (pintype "bidirectional"))
      (node (ref "SPV_5") (pin "8") (pinfunction "XSHUT_8") (pintype "bidirectional"))
    )
    (net (code "43") (name "Net-(SPV_5-VCTRL)") (class "Default")
      (node (ref "C17") (pin "1") (pinfunction "1_1") (pintype "passive"))
      (node (ref "R19") (pin "1") (pinfunction "1_1") (pintype "passive"))
      (node (ref "R20") (pin "2") (pinfunction "2_2") (pintype "passive"))
      (node (ref "SPV_5") (pin "5") (pinfunction "VCTRL_5") (pintype "bidirectional"))
    )
    (net (code "44") (name "Net-(SPV_5-VOUT)") (class "Default")
      (node (ref "C16") (pin "1") (pinfunction "1_1") (pintype "passive"))
      (node (ref "R21") (pin "1") (pinfunction "1_1") (pintype "passive"))
      (node (ref "R22") (pin "2") (pinfunction "2_2") (pintype "passive"))
      (node (ref "SPV_5") (pin "4") (pinfunction "VOUT_4") (pintype "bidirectional"))
    )
    (net (code "45") (name "Net-(SPV_6-ICTRL+)") (class "Default")
      (node (ref "C26") (pin "1") (pinfunction "1_1") (pintype "passive"))
      (node (ref "R34") (pin "1") (pinfunction "1_1") (pintype "passive"))
      (node (ref "SPV_6") (pin "7") (pinfunction "ICTRL+_7") (pintype "bidirectional"))
    )
    (net (code "46") (name "Net-(SPV_6-ICTRL-)") (class "Default")
      (node (ref "C26") (pin "2") (pinfunction "2_2") (pintype "passive"))
      (node (ref "R36") (pin "1") (pinfunction "1_1") (pintype "passive"))
      (node (ref "SPV_6") (pin "6") (pinfunction "ICTRL-_6") (pintype "bidirectional"))
    )
    (net (code "47") (name "Net-(SPV_6-LX)") (class "Default")
      (node (ref "L6") (pin "2") (pinfunction "2_2") (pintype "passive"))
      (node (ref "SPV_6") (pin "3") (pinfunction "LX_3") (pintype "bidirectional"))
    )
    (net (code "48") (name "Net-(SPV_6-MPP-SET)") (class "Default")
      (node (ref "C28") (pin "1") (pinfunction "1_1") (pintype "passive"))
      (node (ref "R35") (pin "1") (pinfunction "1_1") (pintype "passive"))
      (node (ref "SPV_6") (pin "1") (pinfunction "MPP-SET_1") (pintype "bidirectional"))
      (node (ref "SPV_6") (pin "8") (pinfunction "XSHUT_8") (pintype "bidirectional"))
    )
    (net (code "49") (name "Net-(SPV_6-VCTRL)") (class "Default")
      (node (ref "C30") (pin "1") (pinfunction "1_1") (pintype "passive"))
      (node (ref "R31") (pin "1") (pinfunction "1_1") (pintype "passive"))
      (node (ref "R32") (pin "2") (pinfunction "2_2") (pintype "passive"))
      (node (ref "SPV_6") (pin "5") (pinfunction "VCTRL_5") (pintype "bidirectional"))
    )
    (net (code "50") (name "Net-(SPV_6-VOUT)") (class "Default")
      (node (ref "C29") (pin "1") (pinfunction "1_1") (pintype "passive"))
      (node (ref "R33") (pin "1") (pinfunction "1_1") (pintype "passive"))
      (node (ref "R34") (pin "2") (pinfunction "2_2") (pintype "passive"))
      (node (ref "SPV_6") (pin "4") (pinfunction "VOUT_4") (pintype "bidirectional"))
    )
    (net (code "51") (name "unconnected-(J3-Pad5)") (class "Default")
      (node (ref "J3") (pin "5") (pinfunction "5_5") (pintype "passive"))
    )
    (net (code "52") (name "unconnected-(J3-Pad6)") (class "Default")
      (node (ref "J3") (pin "6") (pinfunction "6_6") (pintype "passive"))
    )
    (net (code "53") (name "unconnected-(J3-Pad7)") (class "Default")
      (node (ref "J3") (pin "7") (pinfunction "7_7") (pintype "passive"))
    )
    (net (code "54") (name "unconnected-(J3-Pad8)") (class "Default")
      (node (ref "J3") (pin "8") (pinfunction "8_8") (pintype "passive"))
    )
  )
)
